# Led_Status.net
KiCad netlist of a schematic drawn in Altium Designer
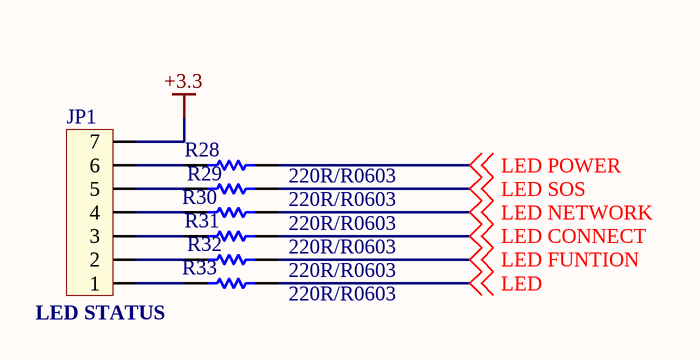
[diagram p0: Led Status.SchDoc]

(export (version "E")
  (design (tool "Eeschema 10.0.6"))
  (components
    (comp (ref "JP1")
      (value "LED STATUS")
      (footprint "LED_VIEW_SMD")
      (description "Connector 7")
      (libsource (lib "thu vien 3d") (part "Header7"))
    )
    (comp (ref "R28")
      (value "220R/R0603")
      (footprint "Manh_Resistor:R0603")
      (description "RES SMD 220 OHM 1% 1/10W 0603")
      (fields
        (field (name "MANUFACTURER") "Yageo")
        (field (name "MANUFACTURER PART NUMBER") "RC0603JR-07220RL")
      )
      (libsource (lib "Manh_Resistor") (part "220R/R0603/1%"))
    )
    (comp (ref "R29")
      (value "220R/R0603")
      (footprint "Manh_Resistor:R0603")
      (description "RES SMD 220 OHM 1% 1/10W 0603")
      (fields
        (field (name "MANUFACTURER") "Yageo")
        (field (name "MANUFACTURER PART NUMBER") "RC0603JR-07220RL")
      )
      (libsource (lib "Manh_Resistor") (part "220R/R0603/1%"))
    )
    (comp (ref "R30")
      (value "220R/R0603")
      (footprint "Manh_Resistor:R0603")
      (description "RES SMD 220 OHM 1% 1/10W 0603")
      (fields
        (field (name "MANUFACTURER") "Yageo")
        (field (name "MANUFACTURER PART NUMBER") "RC0603JR-07220RL")
      )
      (libsource (lib "Manh_Resistor") (part "220R/R0603/1%"))
    )
    (comp (ref "R31")
      (value "220R/R0603")
      (footprint "Manh_Resistor:R0603")
      (description "RES SMD 220 OHM 1% 1/10W 0603")
      (fields
        (field (name "MANUFACTURER") "Yageo")
        (field (name "MANUFACTURER PART NUMBER") "RC0603JR-07220RL")
      )
      (libsource (lib "Manh_Resistor") (part "220R/R0603/1%"))
    )
    (comp (ref "R32")
      (value "220R/R0603")
      (footprint "Manh_Resistor:R0603")
      (description "RES SMD 220 OHM 1% 1/10W 0603")
      (fields
        (field (name "MANUFACTURER") "Yageo")
        (field (name "MANUFACTURER PART NUMBER") "RC0603JR-07220RL")
      )
      (libsource (lib "Manh_Resistor") (part "220R/R0603/1%"))
    )
    (comp (ref "R33")
      (value "220R/R0603")
      (footprint "Manh_Resistor:R0603")
      (description "RES SMD 220 OHM 1% 1/10W 0603")
      (fields
        (field (name "MANUFACTURER") "Yageo")
        (field (name "MANUFACTURER PART NUMBER") "RC0603JR-07220RL")
      )
      (libsource (lib "Manh_Resistor") (part "220R/R0603/1%"))
    )
  )
  (nets
    (net (code "1") (name "+3.3") (class "Default")
      (node (ref "JP1") (pin "7") (pinfunction "7_7") (pintype "passive"))
    )
    (net (code "2") (name "LED") (class "Default")
      (node (ref "R33") (pin "2") (pinfunction "2_2") (pintype "passive"))
    )
    (net (code "3") (name "LED CONNECT") (class "Default")
      (node (ref "R31") (pin "2") (pinfunction "2_2") (pintype "passive"))
    )
    (net (code "4") (name "LED FUNTION") (class "Default")
      (node (ref "R32") (pin "2") (pinfunction "2_2") (pintype "passive"))
    )
    (net (code "5") (name "LED NETWORK") (class "Default")
      (node (ref "R30") (pin "2") (pinfunction "2_2") (pintype "passive"))
    )
    (net (code "6") (name "LED POWER") (class "Default")
      (node (ref "R28") (pin "2") (pinfunction "2_2") (pintype "passive"))
    )
    (net (code "7") (name "LED SOS") (class "Default")
      (node (ref "R29") (pin "2") (pinfunction "2_2") (pintype "passive"))
    )
    (net (code "8") (name "Net-(JP1-Pad1)") (class "Default")
      (node (ref "JP1") (pin "1") (pinfunction "1_1") (pintype "passive"))
      (node (ref "R33") (pin "1") (pinfunction "1_1") (pintype "passive"))
    )
    (net (code "9") (name "Net-(JP1-Pad2)") (class "Default")
      (node (ref "JP1") (pin "2") (pinfunction "2_2") (pintype "passive"))
      (node (ref "R32") (pin "1") (pinfunction "1_1") (pintype "passive"))
    )
    (net (code "10") (name "Net-(JP1-Pad3)") (class "Default")
      (node (ref "JP1") (pin "3") (pinfunction "3_3") (pintype "passive"))
      (node (ref "R31") (pin "1") (pinfunction "1_1") (pintype "passive"))
    )
    (net (code "11") (name "Net-(JP1-Pad4)") (class "Default")
      (node (ref "JP1") (pin "4") (pinfunction "4_4") (pintype "passive"))
      (node (ref "R30") (pin "1") (pinfunction "1_1") (pintype "passive"))
    )
    (net (code "12") (name "Net-(JP1-Pad5)") (class "Default")
      (node (ref "JP1") (pin "5") (pinfunction "5_5") (pintype "passive"))
      (node (ref "R29") (pin "1") (pinfunction "1_1") (pintype "passive"))
    )
    (net (code "13") (name "Net-(JP1-Pad6)") (class "Default")
      (node (ref "JP1") (pin "6") (pinfunction "6_6") (pintype "passive"))
      (node (ref "R28") (pin "1") (pinfunction "1_1") (pintype "passive"))
    )
  )
)
